# power.net
KiCad netlist of a schematic drawn in EAGLE
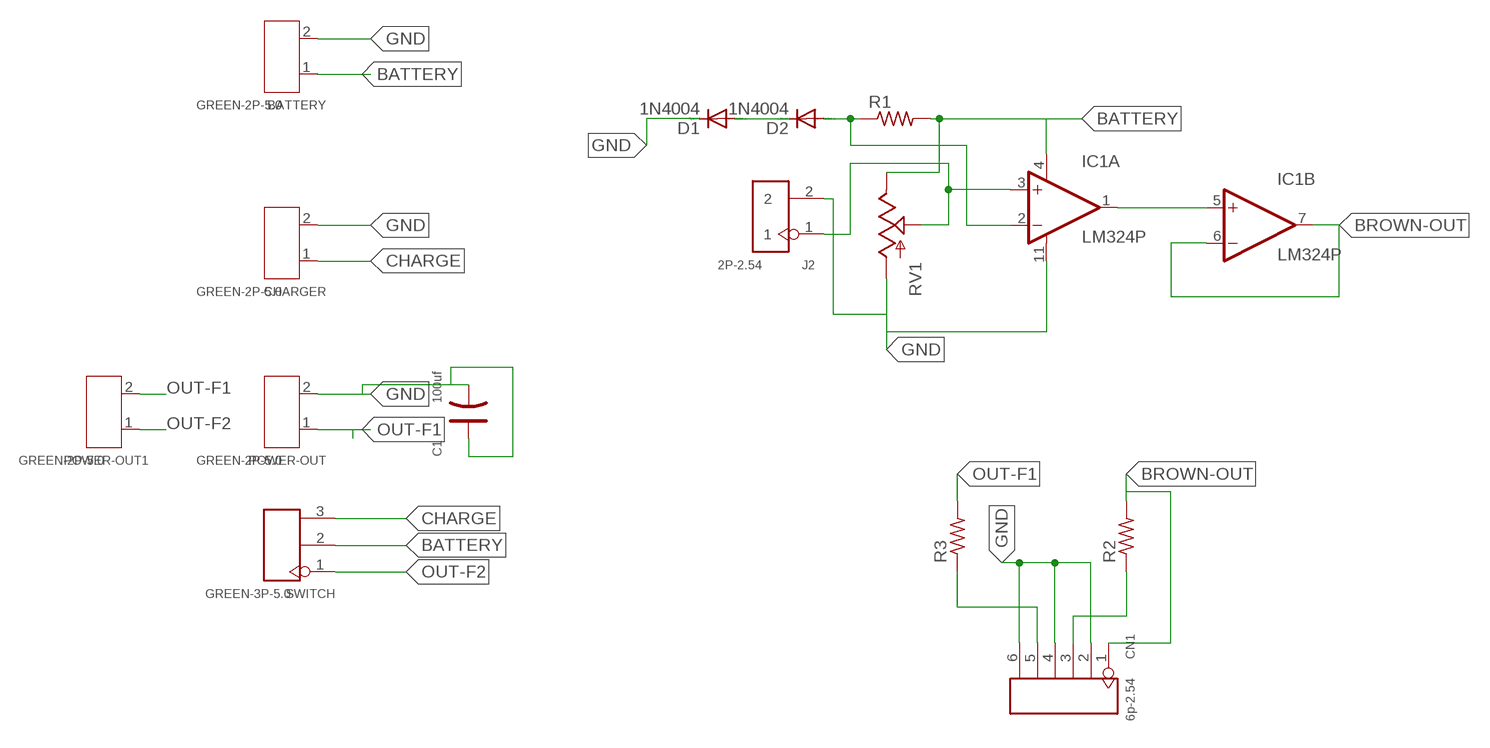
[diagram p0: schematic, sheet 1]

(export (version "E")
  (design (tool "Eeschema 10.0.6"))
  (components
    (comp (ref "BATTERY")
      (value "GREEN-2P-5.0")
      (footprint "eagle-import:H2-5.0-10.5X8.0MM")
      (libsource (lib "eagle-import") (part "SCREW-TERMINAL-GREEN(2P-5.0)"))
    )
    (comp (ref "C1")
      (value "100uf")
      (footprint "eagle-import:PC-D5.3MM")
      (fields (field (name "MPN") "KS 100uF/16V"))
      (libsource (lib "eagle-import") (part "DIP-ALUMINUM-100UF-16V(D5-H7MM)"))
    )
    (comp (ref "CHARGER")
      (value "GREEN-2P-5.0")
      (footprint "eagle-import:H2-5.0-10.5X8.0MM")
      (libsource (lib "eagle-import") (part "SCREW-TERMINAL-GREEN(2P-5.0)"))
    )
    (comp (ref "CN1")
      (value "6p-2.54")
      (footprint "eagle-import:H6-2.54")
      (fields (field (name "MPN") "F185-1106A1BSYC1"))
      (libsource (lib "eagle-import") (part "DIP-BLACK-FEMALE-HEADER-VERT(6P-2.54)"))
    )
    (comp (ref "D1")
      (value "1N4004")
      (footprint "eagle-import:DO41-10")
      (libsource (lib "eagle-import") (part "1N4004"))
    )
    (comp (ref "D2")
      (value "1N4004")
      (footprint "eagle-import:DO41-10")
      (libsource (lib "eagle-import") (part "1N4004"))
    )
    (comp (ref "IC1")
      (value "LM324P")
      (footprint "eagle-import:DIL14")
      (libsource (lib "eagle-import") (part "LM324P"))
    )
    (comp (ref "J2")
      (value "2P-2.54")
      (footprint "eagle-import:H2-2.54")
      (fields (field (name "MPN") "P125-1102A0BS116A3"))
      (libsource (lib "eagle-import") (part "DIP-WHITE-MALE-HEADER-VERT(2P-2.54)"))
    )
    (comp (ref "POWER-OUT")
      (value "GREEN-2P-5.0")
      (footprint "eagle-import:H2-5.0-10.5X8.0MM")
      (libsource (lib "eagle-import") (part "SCREW-TERMINAL-GREEN(2P-5.0)"))
    )
    (comp (ref "POWER-OUT1")
      (value "GREEN-2P-5.0")
      (footprint "eagle-import:H2-5.0-10.5X8.0MM")
      (libsource (lib "eagle-import") (part "SCREW-TERMINAL-GREEN(2P-5.0)"))
    )
    (comp (ref "R1")
      (value "R-US_0207/10")
      (footprint "eagle-import:0207_10")
      (libsource (lib "eagle-import") (part "R-US_0207/10"))
    )
    (comp (ref "R2")
      (value "R-US_0207/10")
      (footprint "eagle-import:0207_10")
      (libsource (lib "eagle-import") (part "R-US_0207/10"))
    )
    (comp (ref "R3")
      (value "R-US_0207/10")
      (footprint "eagle-import:0207_10")
      (libsource (lib "eagle-import") (part "R-US_0207/10"))
    )
    (comp (ref "RV1")
      (value "POTTRIM")
      (footprint "eagle-import:TRIM_POT")
      (libsource (lib "eagle-import") (part "POTTRIM"))
    )
    (comp (ref "SWITCH")
      (value "GREEN-3P-5.0")
      (footprint "eagle-import:H3-5.0-15.5X8.0MM")
      (libsource (lib "eagle-import") (part "SCREW-TERMINAL-GREEN(3P-5.0)"))
    )
  )
  (nets
    (net (code "1") (name "BATTERY") (class "Default")
      (node (ref "BATTERY") (pin "1") (pinfunction "1_1") (pintype "bidirectional"))
      (node (ref "IC1") (pin "4") (pinfunction "V+_4") (pintype "power_in"))
      (node (ref "R1") (pin "2") (pinfunction "2_2") (pintype "passive"))
      (node (ref "RV1") (pin "2") (pinfunction "E_2") (pintype "passive"))
      (node (ref "SWITCH") (pin "2") (pinfunction "P$2_2") (pintype "bidirectional"))
    )
    (net (code "2") (name "BROWN-OUT") (class "Default")
      (node (ref "CN1") (pin "1") (pinfunction "1_1") (pintype "bidirectional"))
      (node (ref "IC1") (pin "6") (pinfunction "-IN_6") (pintype "input"))
      (node (ref "IC1") (pin "7") (pinfunction "OUT_7") (pintype "output"))
      (node (ref "R2") (pin "2") (pinfunction "2_2") (pintype "passive"))
    )
    (net (code "3") (name "CHARGE") (class "Default")
      (node (ref "CHARGER") (pin "1") (pinfunction "1_1") (pintype "bidirectional"))
      (node (ref "SWITCH") (pin "3") (pinfunction "P$3_3") (pintype "bidirectional"))
    )
    (net (code "4") (name "GND") (class "Default")
      (node (ref "BATTERY") (pin "2") (pinfunction "2_2") (pintype "bidirectional"))
      (node (ref "C1") (pin "+") (pinfunction "+_+") (pintype "passive"))
      (node (ref "C1") (pin "-") (pinfunction "-_-") (pintype "passive"))
      (node (ref "CHARGER") (pin "2") (pinfunction "2_2") (pintype "bidirectional"))
      (node (ref "CN1") (pin "2") (pinfunction "2_2") (pintype "bidirectional"))
      (node (ref "CN1") (pin "4") (pinfunction "4_4") (pintype "bidirectional"))
      (node (ref "CN1") (pin "6") (pinfunction "6_6") (pintype "bidirectional"))
      (node (ref "D1") (pin "C") (pinfunction "C_C") (pintype "passive"))
      (node (ref "IC1") (pin "11") (pinfunction "V-_11") (pintype "power_in"))
      (node (ref "J2") (pin "2") (pinfunction "2_2") (pintype "bidirectional"))
      (node (ref "POWER-OUT") (pin "2") (pinfunction "2_2") (pintype "bidirectional"))
      (node (ref "RV1") (pin "3") (pinfunction "A_3") (pintype "passive"))
    )
    (net (code "5") (name "Net-(CN1-Pad3)") (class "Default")
      (node (ref "CN1") (pin "3") (pinfunction "3_3") (pintype "bidirectional"))
      (node (ref "R2") (pin "1") (pinfunction "1_1") (pintype "passive"))
    )
    (net (code "6") (name "Net-(CN1-Pad5)") (class "Default")
      (node (ref "CN1") (pin "5") (pinfunction "5_5") (pintype "bidirectional"))
      (node (ref "R3") (pin "1") (pinfunction "1_1") (pintype "passive"))
    )
    (net (code "7") (name "Net-(D1-PadA)") (class "Default")
      (node (ref "D1") (pin "A") (pinfunction "A_A") (pintype "passive"))
      (node (ref "D2") (pin "C") (pinfunction "C_C") (pintype "passive"))
    )
    (net (code "8") (name "Net-(IC1A-+IN)") (class "Default")
      (node (ref "IC1") (pin "3") (pinfunction "+IN_3") (pintype "input"))
      (node (ref "J2") (pin "1") (pinfunction "1_1") (pintype "bidirectional"))
      (node (ref "RV1") (pin "1") (pinfunction "S_1") (pintype "passive"))
    )
    (net (code "9") (name "Net-(IC1A--IN)") (class "Default")
      (node (ref "D2") (pin "A") (pinfunction "A_A") (pintype "passive"))
      (node (ref "IC1") (pin "2") (pinfunction "-IN_2") (pintype "input"))
      (node (ref "R1") (pin "1") (pinfunction "1_1") (pintype "passive"))
    )
    (net (code "10") (name "Net-(IC1A-OUT)") (class "Default")
      (node (ref "IC1") (pin "1") (pinfunction "OUT_1") (pintype "output"))
      (node (ref "IC1") (pin "5") (pinfunction "+IN_5") (pintype "input"))
    )
    (net (code "11") (name "OUT-F1") (class "Default")
      (node (ref "POWER-OUT") (pin "1") (pinfunction "1_1") (pintype "bidirectional"))
      (node (ref "POWER-OUT1") (pin "2") (pinfunction "2_2") (pintype "bidirectional"))
      (node (ref "R3") (pin "2") (pinfunction "2_2") (pintype "passive"))
    )
    (net (code "12") (name "OUT-F2") (class "Default")
      (node (ref "POWER-OUT1") (pin "1") (pinfunction "1_1") (pintype "bidirectional"))
      (node (ref "SWITCH") (pin "1") (pinfunction "P$1_1") (pintype "bidirectional"))
    )
  )
)
